# SimpleSwitch.net
KiCad netlist of a schematic drawn in EAGLE
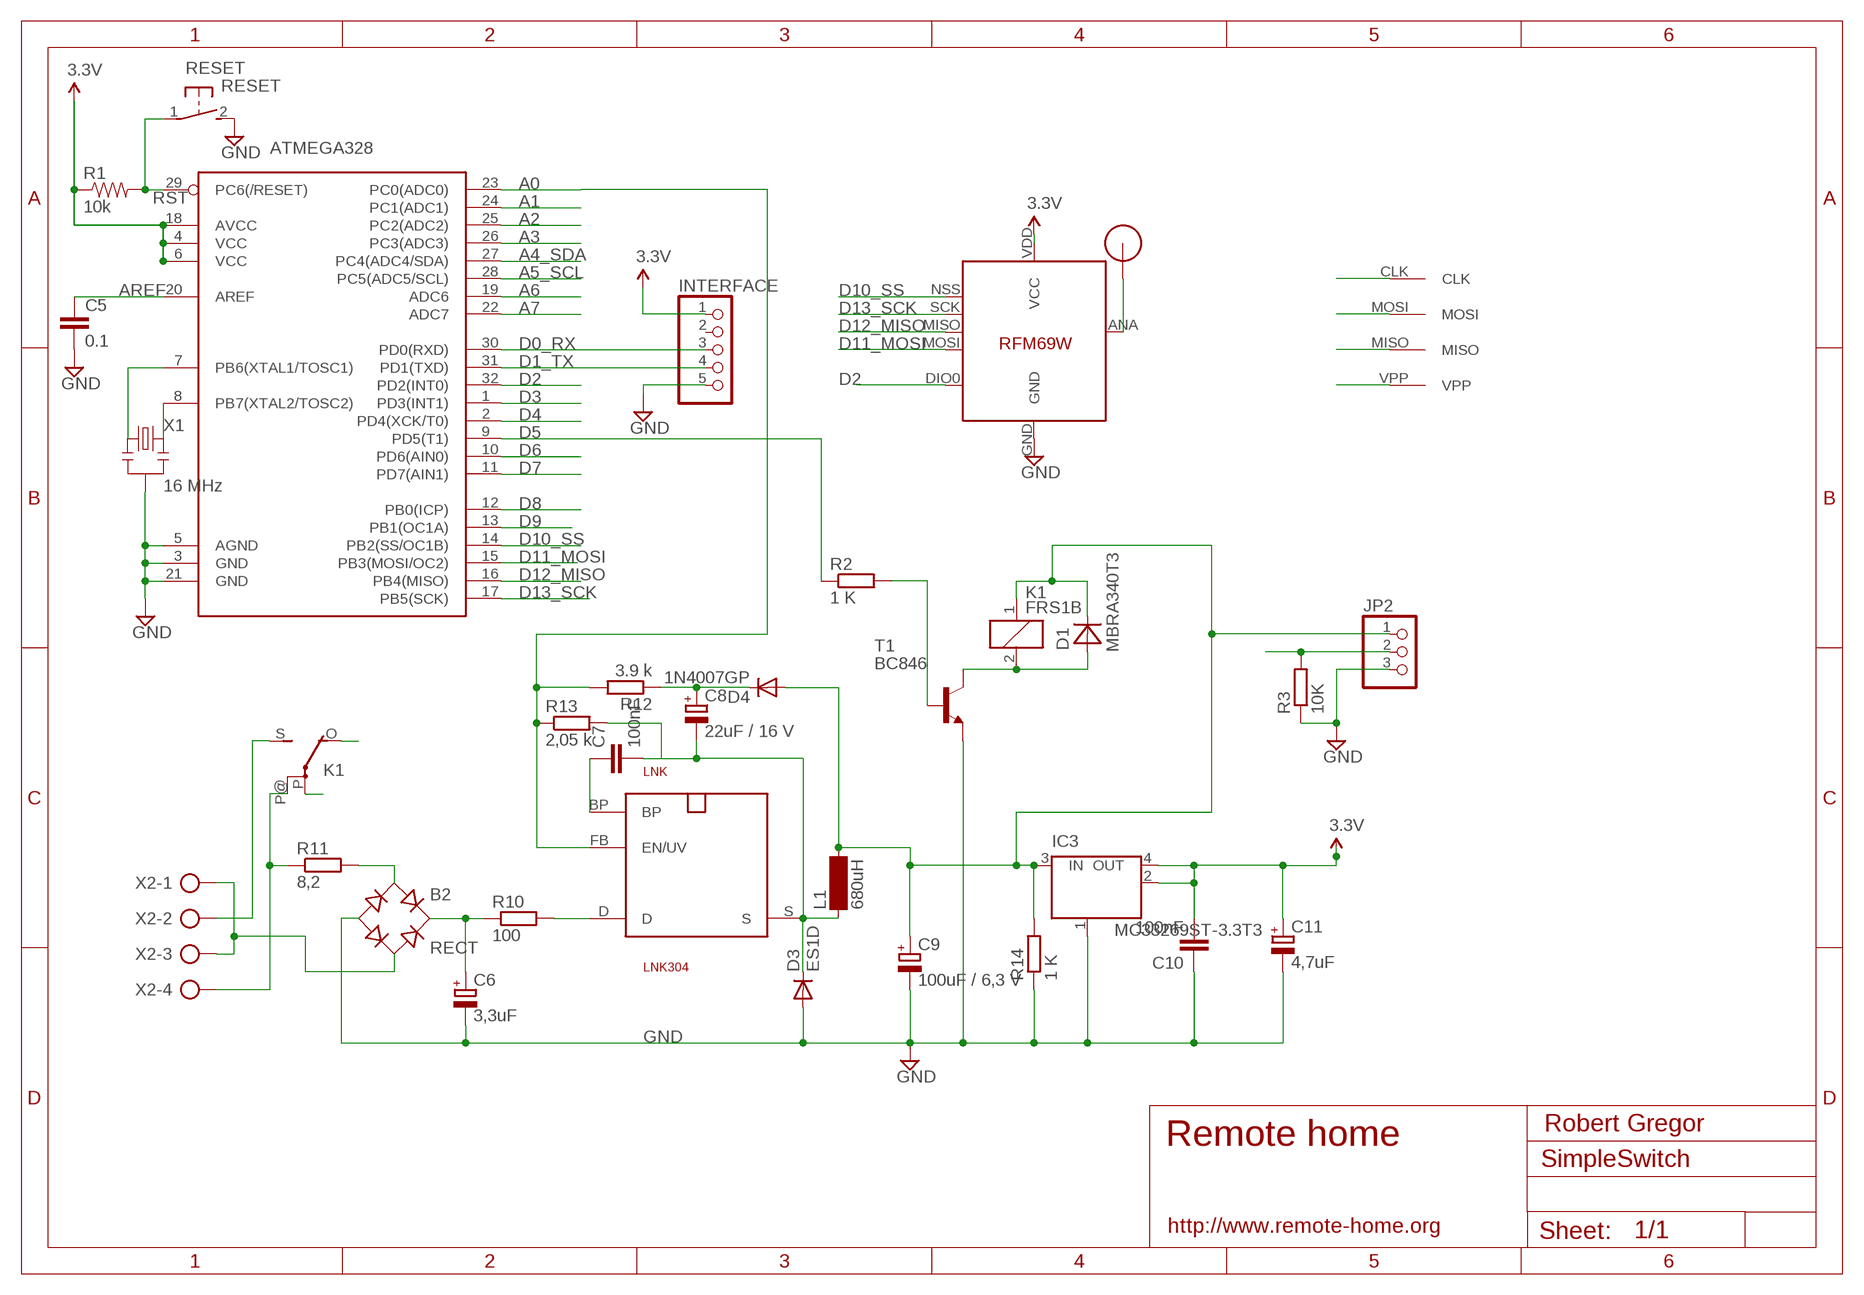
[diagram p0: schematic, sheet 1]

(export (version "E")
  (design (tool "Eeschema 10.0.6"))
  (components
    (comp (ref "ATMEGA328")
      (value "ATMega-328")
      (footprint "eagle-import:TQFP32-08")
      (libsource (lib "eagle-import") (part "ATMEGA168/328TQFP32"))
    )
    (comp (ref "B2")
      (value "RECT")
      (footprint "eagle-import:TO-269AA")
      (libsource (lib "eagle-import") (part "RECTIFIER-S40"))
    )
    (comp (ref "C5")
      (value "0.1")
      (footprint "eagle-import:0603-CAP")
      (libsource (lib "eagle-import") (part "CAP0603-CAP"))
    )
    (comp (ref "C6")
      (value "3,3uF")
      (footprint "eagle-import:E5-10,5")
      (libsource (lib "eagle-import") (part "CPOL-EUE5-10.5"))
    )
    (comp (ref "C7")
      (value "100nF")
      (footprint "eagle-import:C2012")
      (libsource (lib "eagle-import") (part "C-EUC2012"))
    )
    (comp (ref "C8")
      (value "22uF / 16 V")
      (footprint "eagle-import:SMC_C")
      (libsource (lib "eagle-import") (part "CPOL-EUSMCC"))
    )
    (comp (ref "C9")
      (value "100uF / 6,3 V")
      (footprint "eagle-import:E2,5-5")
      (libsource (lib "eagle-import") (part "CPOL-EUE2.5-5"))
    )
    (comp (ref "C10")
      (value "100nF")
      (footprint "eagle-import:C2012")
      (libsource (lib "eagle-import") (part "C-EUC2012"))
    )
    (comp (ref "C11")
      (value "4,7uF")
      (footprint "eagle-import:SMC_A")
      (libsource (lib "eagle-import") (part "CPOL-EUSMCA"))
    )
    (comp (ref "D1")
      (value "MBRA340T3")
      (footprint "eagle-import:SMA")
      (libsource (lib "eagle-import") (part "MBRA340T3"))
    )
    (comp (ref "D3")
      (value "ES1D")
      (footprint "eagle-import:DO214AC")
      (libsource (lib "eagle-import") (part "DIODE-DO214AC"))
    )
    (comp (ref "D4")
      (value "1N4007GP")
      (footprint "eagle-import:DO214AA")
      (libsource (lib "eagle-import") (part "DIODE-DO214AA"))
    )
    (comp (ref "IC3")
      (value "MC33269ST-3.3T3")
      (footprint "eagle-import:SOT223")
      (libsource (lib "eagle-import") (part "MC33269ST-3.3T3"))
    )
    (comp (ref "INTERFACE")
      (value "PINHD-1X5")
      (footprint "eagle-import:1X05")
      (libsource (lib "eagle-import") (part "PINHD-1X5"))
    )
    (comp (ref "JP2")
      (value "PINHD-1X3")
      (footprint "eagle-import:1X03")
      (libsource (lib "eagle-import") (part "PINHD-1X3"))
    )
    (comp (ref "K1")
      (value "FRS1B")
      (footprint "eagle-import:FRS1B")
      (libsource (lib "eagle-import") (part "FRS1B"))
    )
    (comp (ref "L1")
      (value "680uH")
      (footprint "eagle-import:BS11")
      (libsource (lib "eagle-import") (part "BS11"))
    )
    (comp (ref "LNK")
      (value "LNK304")
      (footprint "eagle-import:SO-8C")
      (libsource (lib "eagle-import") (part "SO-8C"))
    )
    (comp (ref "R1")
      (value "10k")
      (footprint "eagle-import:0603-RES")
      (libsource (lib "eagle-import") (part "RESISTOR0603-RES"))
    )
    (comp (ref "R2")
      (value "1 K")
      (footprint "eagle-import:M2012")
      (libsource (lib "eagle-import") (part "R-EU_M2012"))
    )
    (comp (ref "R3")
      (value "10K")
      (footprint "eagle-import:M2012")
      (libsource (lib "eagle-import") (part "R-EU_M2012"))
    )
    (comp (ref "R10")
      (value "100")
      (footprint "eagle-import:R2512W")
      (libsource (lib "eagle-import") (part "R-EU_R2512W"))
    )
    (comp (ref "R11")
      (value "8,2")
      (footprint "eagle-import:0411_12")
      (libsource (lib "eagle-import") (part "R-EU_0411/12"))
    )
    (comp (ref "R12")
      (value "3.9 k")
      (footprint "eagle-import:M2012")
      (libsource (lib "eagle-import") (part "R-EU_M2012"))
    )
    (comp (ref "R13")
      (value "2,05 k")
      (footprint "eagle-import:M2012")
      (libsource (lib "eagle-import") (part "R-EU_M2012"))
    )
    (comp (ref "R14")
      (value "1 K")
      (footprint "eagle-import:M2012")
      (libsource (lib "eagle-import") (part "R-EU_M2012"))
    )
    (comp (ref "RESET")
      (value "RESET")
      (footprint "eagle-import:DTSM-3")
      (libsource (lib "eagle-import") (part "DTSM-3"))
    )
    (comp (ref "RFM69")
      (value "RFM69")
      (footprint "eagle-import:RFM69W-MINPADS")
      (libsource (lib "eagle-import") (part "RFM69"))
    )
    (comp (ref "T1")
      (value "BC846")
      (footprint "eagle-import:SOT23")
      (libsource (lib "eagle-import") (part "BC846"))
    )
    (comp (ref "U$1")
      (value "RFM12B_ANTENNA")
      (footprint "eagle-import:RFM12B-ANTENNA")
      (libsource (lib "eagle-import") (part "RFM12B_ANTENNA"))
    )
    (comp (ref "U$2")
      (value "AVRHEADERDIP")
      (footprint "eagle-import:AVRHEADER")
      (libsource (lib "eagle-import") (part "AVRHEADERDIP"))
    )
    (comp (ref "X1")
      (value "16 MHz")
      (footprint "eagle-import:RESONATOR-SMD")
      (libsource (lib "eagle-import") (part "RESONATORSMD"))
    )
    (comp (ref "X2")
      (value "AK500/4")
      (footprint "eagle-import:AK500_4")
      (libsource (lib "eagle-import") (part "AK500/4"))
    )
  )
  (nets
    (net (code "1") (name "/A0") (class "Default")
      (node (ref "ATMEGA328") (pin "23") (pinfunction "PC0(ADC0)_23") (pintype "bidirectional"))
      (node (ref "LNK") (pin "FB") (pinfunction "EN/UV_FB") (pintype "input"))
      (node (ref "R12") (pin "2") (pinfunction "2_2") (pintype "passive"))
      (node (ref "R13") (pin "1") (pinfunction "1_1") (pintype "passive"))
    )
    (net (code "2") (name "/A1") (class "Default")
      (node (ref "ATMEGA328") (pin "24") (pinfunction "PC1(ADC1)_24") (pintype "bidirectional"))
    )
    (net (code "3") (name "/A2") (class "Default")
      (node (ref "ATMEGA328") (pin "25") (pinfunction "PC2(ADC2)_25") (pintype "bidirectional"))
    )
    (net (code "4") (name "/A3") (class "Default")
      (node (ref "ATMEGA328") (pin "26") (pinfunction "PC3(ADC3)_26") (pintype "bidirectional"))
    )
    (net (code "5") (name "/A4_SDA") (class "Default")
      (node (ref "ATMEGA328") (pin "27") (pinfunction "PC4(ADC4/SDA)_27") (pintype "bidirectional"))
    )
    (net (code "6") (name "/A5_SCL") (class "Default")
      (node (ref "ATMEGA328") (pin "28") (pinfunction "PC5(ADC5/SCL)_28") (pintype "bidirectional"))
    )
    (net (code "7") (name "/A6") (class "Default")
      (node (ref "ATMEGA328") (pin "19") (pinfunction "ADC6_19") (pintype "bidirectional"))
    )
    (net (code "8") (name "/A7") (class "Default")
      (node (ref "ATMEGA328") (pin "22") (pinfunction "ADC7_22") (pintype "bidirectional"))
    )
    (net (code "9") (name "/AREF") (class "Default")
      (node (ref "ATMEGA328") (pin "20") (pinfunction "AREF_20") (pintype "bidirectional"))
      (node (ref "C5") (pin "1") (pinfunction "1_1") (pintype "passive"))
    )
    (net (code "10") (name "/D0_RX") (class "Default")
      (node (ref "ATMEGA328") (pin "30") (pinfunction "PD0(RXD)_30") (pintype "bidirectional"))
      (node (ref "INTERFACE") (pin "3") (pinfunction "3_3") (pintype "passive"))
    )
    (net (code "11") (name "/D1_TX") (class "Default")
      (node (ref "ATMEGA328") (pin "31") (pinfunction "PD1(TXD)_31") (pintype "bidirectional"))
      (node (ref "INTERFACE") (pin "4") (pinfunction "4_4") (pintype "passive"))
    )
    (net (code "12") (name "/D2") (class "Default")
      (node (ref "ATMEGA328") (pin "32") (pinfunction "PD2(INT0)_32") (pintype "bidirectional"))
      (node (ref "RFM69") (pin "DIO0") (pinfunction "DIO0_DIO0") (pintype "open_collector"))
    )
    (net (code "13") (name "/D3") (class "Default")
      (node (ref "ATMEGA328") (pin "1") (pinfunction "PD3(INT1)_1") (pintype "bidirectional"))
      (node (ref "JP2") (pin "2") (pinfunction "2_2") (pintype "passive"))
      (node (ref "R3") (pin "2") (pinfunction "2_2") (pintype "passive"))
    )
    (net (code "14") (name "/D4") (class "Default")
      (node (ref "ATMEGA328") (pin "2") (pinfunction "PD4(XCK/T0)_2") (pintype "bidirectional"))
    )
    (net (code "15") (name "/D5") (class "Default")
      (node (ref "ATMEGA328") (pin "9") (pinfunction "PD5(T1)_9") (pintype "bidirectional"))
      (node (ref "R2") (pin "1") (pinfunction "1_1") (pintype "passive"))
    )
    (net (code "16") (name "/D6") (class "Default")
      (node (ref "ATMEGA328") (pin "10") (pinfunction "PD6(AIN0)_10") (pintype "bidirectional"))
    )
    (net (code "17") (name "/D7") (class "Default")
      (node (ref "ATMEGA328") (pin "11") (pinfunction "PD7(AIN1)_11") (pintype "bidirectional"))
    )
    (net (code "18") (name "/D8") (class "Default")
      (node (ref "ATMEGA328") (pin "12") (pinfunction "PB0(ICP)_12") (pintype "bidirectional"))
    )
    (net (code "19") (name "/D9") (class "Default")
      (node (ref "ATMEGA328") (pin "13") (pinfunction "PB1(OC1A)_13") (pintype "bidirectional"))
    )
    (net (code "20") (name "/D10_SS") (class "Default")
      (node (ref "ATMEGA328") (pin "14") (pinfunction "PB2(SS/OC1B)_14") (pintype "bidirectional"))
      (node (ref "RFM69") (pin "NSS") (pinfunction "SEL_NSS") (pintype "input"))
    )
    (net (code "21") (name "/D11_MOSI") (class "Default")
      (node (ref "ATMEGA328") (pin "15") (pinfunction "PB3(MOSI/OC2)_15") (pintype "bidirectional"))
      (node (ref "RFM69") (pin "MOSI") (pinfunction "MOSI_MOSI") (pintype "output"))
      (node (ref "U$2") (pin "MOSI") (pinfunction "MOSI_MOSI") (pintype "bidirectional"))
    )
    (net (code "22") (name "/D12_MISO") (class "Default")
      (node (ref "ATMEGA328") (pin "16") (pinfunction "PB4(MISO)_16") (pintype "bidirectional"))
      (node (ref "RFM69") (pin "MISO") (pinfunction "MISO_MISO") (pintype "input"))
      (node (ref "U$2") (pin "MISO") (pinfunction "MISO_MISO") (pintype "bidirectional"))
    )
    (net (code "23") (name "/D13_SCK") (class "Default")
      (node (ref "ATMEGA328") (pin "17") (pinfunction "PB5(SCK)_17") (pintype "bidirectional"))
      (node (ref "RFM69") (pin "SCK") (pinfunction "SCK_SCK") (pintype "input"))
      (node (ref "U$2") (pin "CLK") (pinfunction "CLK_CLK") (pintype "bidirectional"))
    )
    (net (code "24") (name "/RST") (class "Default")
      (node (ref "ATMEGA328") (pin "29") (pinfunction "PC6(/RESET)_29") (pintype "bidirectional"))
      (node (ref "R1") (pin "2") (pinfunction "2_2") (pintype "passive"))
      (node (ref "RESET") (pin "1") (pinfunction "1_1") (pintype "passive"))
      (node (ref "U$2") (pin "VPP") (pinfunction "VPP_VPP") (pintype "bidirectional"))
    )
    (net (code "25") (name "3.3V") (class "Default")
      (node (ref "ATMEGA328") (pin "18") (pinfunction "AVCC_18") (pintype "bidirectional"))
      (node (ref "ATMEGA328") (pin "4") (pinfunction "VCC_4") (pintype "bidirectional"))
      (node (ref "ATMEGA328") (pin "6") (pinfunction "VCC_6") (pintype "bidirectional"))
      (node (ref "C10") (pin "2") (pinfunction "2_2") (pintype "passive"))
      (node (ref "C11") (pin "+") (pinfunction "+_+") (pintype "passive"))
      (node (ref "IC3") (pin "2") (pinfunction "OUT_2") (pintype "passive"))
      (node (ref "IC3") (pin "4") (pinfunction "OUT_4") (pintype "passive"))
      (node (ref "INTERFACE") (pin "1") (pinfunction "1_1") (pintype "passive"))
      (node (ref "R1") (pin "1") (pinfunction "1_1") (pintype "passive"))
      (node (ref "RFM69") (pin "VDD") (pinfunction "VCC_VDD") (pintype "power_in"))
    )
    (net (code "26") (name "GND") (class "Default")
      (node (ref "ATMEGA328") (pin "21") (pinfunction "GND_21") (pintype "bidirectional"))
      (node (ref "ATMEGA328") (pin "3") (pinfunction "GND_3") (pintype "bidirectional"))
      (node (ref "ATMEGA328") (pin "5") (pinfunction "AGND_5") (pintype "bidirectional"))
      (node (ref "B2") (pin "-") (pinfunction "-_-") (pintype "passive"))
      (node (ref "C10") (pin "1") (pinfunction "1_1") (pintype "passive"))
      (node (ref "C11") (pin "-") (pinfunction "-_-") (pintype "passive"))
      (node (ref "C5") (pin "2") (pinfunction "2_2") (pintype "passive"))
      (node (ref "C6") (pin "-") (pinfunction "-_-") (pintype "passive"))
      (node (ref "C9") (pin "-") (pinfunction "-_-") (pintype "passive"))
      (node (ref "D3") (pin "A") (pinfunction "A_A") (pintype "passive"))
      (node (ref "IC3") (pin "1") (pinfunction "GND/ADJ_1") (pintype "input"))
      (node (ref "INTERFACE") (pin "5") (pinfunction "5_5") (pintype "passive"))
      (node (ref "JP2") (pin "3") (pinfunction "3_3") (pintype "passive"))
      (node (ref "R14") (pin "1") (pinfunction "1_1") (pintype "passive"))
      (node (ref "R3") (pin "1") (pinfunction "1_1") (pintype "passive"))
      (node (ref "RESET") (pin "2") (pinfunction "2_2") (pintype "passive"))
      (node (ref "RFM69") (pin "GND") (pinfunction "GND_GND") (pintype "power_in"))
      (node (ref "T1") (pin "2") (pinfunction "E_2") (pintype "passive"))
      (node (ref "X1") (pin "2") (pinfunction "2_2") (pintype "passive"))
    )
    (net (code "27") (name "Net-(ATMEGA328-PB6(XTAL1{slash}TOSC1))") (class "Default")
      (node (ref "ATMEGA328") (pin "7") (pinfunction "PB6(XTAL1/TOSC1)_7") (pintype "bidirectional"))
      (node (ref "X1") (pin "1") (pinfunction "1_1") (pintype "passive"))
    )
    (net (code "28") (name "Net-(ATMEGA328-PB7(XTAL2{slash}TOSC2))") (class "Default")
      (node (ref "ATMEGA328") (pin "8") (pinfunction "PB7(XTAL2/TOSC2)_8") (pintype "bidirectional"))
      (node (ref "X1") (pin "3") (pinfunction "3_3") (pintype "passive"))
    )
    (net (code "29") (name "Net-(B2-Pad+)") (class "Default")
      (node (ref "B2") (pin "+") (pinfunction "+_+") (pintype "passive"))
      (node (ref "C6") (pin "+") (pinfunction "+_+") (pintype "passive"))
      (node (ref "R10") (pin "1") (pinfunction "1_1") (pintype "passive"))
    )
    (net (code "30") (name "Net-(B2-PadAC1)") (class "Default")
      (node (ref "B2") (pin "AC1") (pinfunction "AC1_AC1") (pintype "passive"))
      (node (ref "R11") (pin "2") (pinfunction "2_2") (pintype "passive"))
    )
    (net (code "31") (name "Net-(C7-Pad1)") (class "Default")
      (node (ref "C7") (pin "1") (pinfunction "1_1") (pintype "passive"))
      (node (ref "LNK") (pin "BP") (pinfunction "BP_BP") (pintype "passive"))
    )
    (net (code "32") (name "Net-(C7-Pad2)") (class "Default")
      (node (ref "C7") (pin "2") (pinfunction "2_2") (pintype "passive"))
      (node (ref "C8") (pin "-") (pinfunction "-_-") (pintype "passive"))
      (node (ref "D3") (pin "C") (pinfunction "C_C") (pintype "passive"))
      (node (ref "L1") (pin "1") (pinfunction "1_1") (pintype "passive"))
      (node (ref "LNK") (pin "S") (pinfunction "S_S") (pintype "power_in"))
      (node (ref "R13") (pin "2") (pinfunction "2_2") (pintype "passive"))
    )
    (net (code "33") (name "Net-(C8-Pad+)") (class "Default")
      (node (ref "C8") (pin "+") (pinfunction "+_+") (pintype "passive"))
      (node (ref "D4") (pin "C") (pinfunction "C_C") (pintype "passive"))
      (node (ref "R12") (pin "1") (pinfunction "1_1") (pintype "passive"))
    )
    (net (code "34") (name "Net-(IC3-IN)") (class "Default")
      (node (ref "C9") (pin "+") (pinfunction "+_+") (pintype "passive"))
      (node (ref "D1") (pin "C") (pinfunction "C_C") (pintype "passive"))
      (node (ref "D4") (pin "A") (pinfunction "A_A") (pintype "passive"))
      (node (ref "IC3") (pin "3") (pinfunction "IN_3") (pintype "input"))
      (node (ref "JP2") (pin "1") (pinfunction "1_1") (pintype "passive"))
      (node (ref "K1") (pin "1") (pinfunction "1_1") (pintype "passive"))
      (node (ref "L1") (pin "2") (pinfunction "2_2") (pintype "passive"))
      (node (ref "R14") (pin "2") (pinfunction "2_2") (pintype "passive"))
    )
    (net (code "35") (name "Net-(LNK-PadD)") (class "Default")
      (node (ref "LNK") (pin "D") (pinfunction "D_D") (pintype "open_collector"))
      (node (ref "R10") (pin "2") (pinfunction "2_2") (pintype "passive"))
    )
    (net (code "36") (name "Net-(RFM69-ANT)") (class "Default")
      (node (ref "RFM69") (pin "ANA") (pinfunction "ANT_ANA") (pintype "passive"))
      (node (ref "U$1") (pin "P$1") (pinfunction "1_P$1") (pintype "bidirectional"))
    )
    (net (code "37") (name "Net-(T1-B)") (class "Default")
      (node (ref "R2") (pin "2") (pinfunction "2_2") (pintype "passive"))
      (node (ref "T1") (pin "1") (pinfunction "B_1") (pintype "passive"))
    )
    (net (code "38") (name "Net-(T1-C)") (class "Default")
      (node (ref "D1") (pin "A") (pinfunction "A_A") (pintype "passive"))
      (node (ref "K1") (pin "2") (pinfunction "2_2") (pintype "passive"))
      (node (ref "T1") (pin "3") (pinfunction "C_3") (pintype "passive"))
    )
    (net (code "39") (name "Net-(X2A-KL)") (class "Default")
      (node (ref "B2") (pin "AC2") (pinfunction "AC2_AC2") (pintype "passive"))
      (node (ref "X2") (pin "1") (pinfunction "KL_1") (pintype "passive"))
      (node (ref "X2") (pin "3") (pinfunction "KL_3") (pintype "passive"))
    )
    (net (code "40") (name "Net-(X2B-KL)") (class "Default")
      (node (ref "K1") (pin "S") (pinfunction "S_S") (pintype "passive"))
      (node (ref "X2") (pin "2") (pinfunction "KL_2") (pintype "passive"))
    )
    (net (code "41") (name "Net-(X2D-KL)") (class "Default")
      (node (ref "K1") (pin "P@") (pinfunction "P_P@") (pintype "passive"))
      (node (ref "R11") (pin "1") (pinfunction "1_1") (pintype "passive"))
      (node (ref "X2") (pin "4") (pinfunction "KL_4") (pintype "passive"))
    )
    (net (code "42") (name "unconnected-(INTERFACE-Pad2)") (class "Default")
      (node (ref "INTERFACE") (pin "2") (pinfunction "2_2") (pintype "passive"))
    )
    (net (code "43") (name "unconnected-(K1-PadO)") (class "Default")
      (node (ref "K1") (pin "O") (pinfunction "O_O") (pintype "passive"))
    )
    (net (code "44") (name "unconnected-(K1-PadP)") (class "Default")
      (node (ref "K1") (pin "P") (pinfunction "P_P") (pintype "passive"))
    )
  )
)
